# H22R2x_Frontend_1.net
KiCad netlist of a schematic drawn in Altium Designer
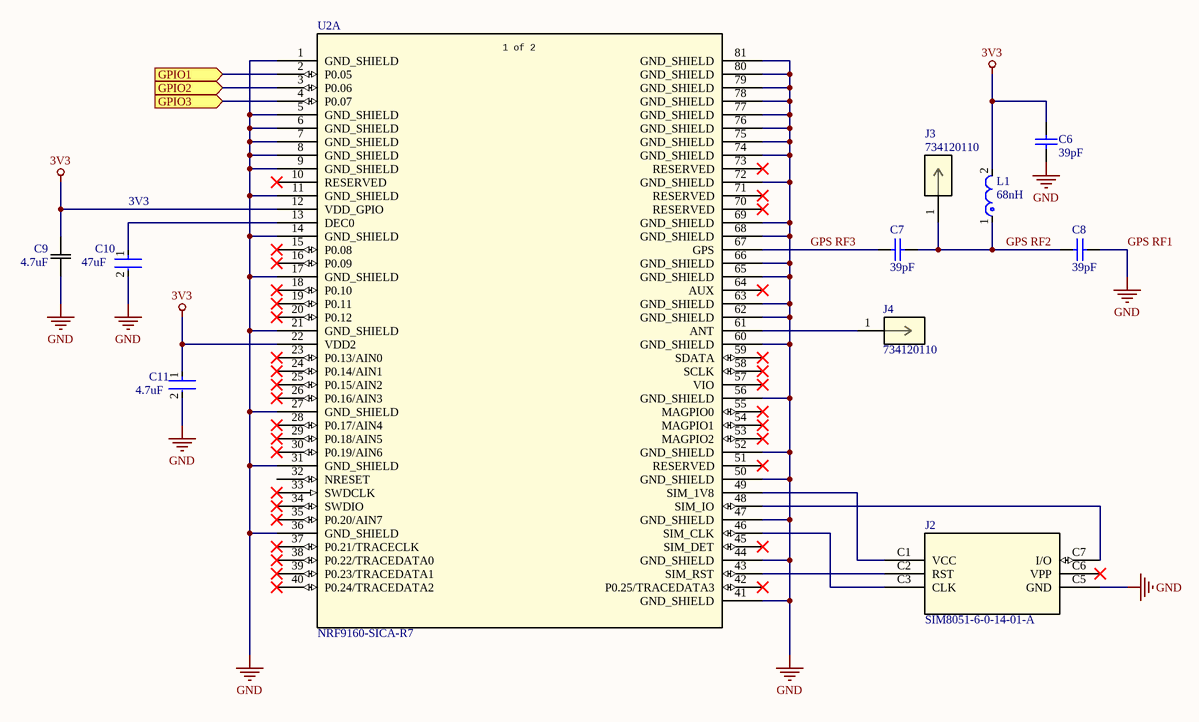
[diagram p0: H22R2x_Frontend 1.SchDoc]

(export (version "E")
  (design (tool "Eeschema 10.0.6"))
  (components
    (comp (ref "C6")
      (value "39pF")
      (footprint "CAPC1005X56X25ML10T15")
      (description "04023A390KAT2A")
      (fields (field (name "MANUFACTURER") "AVX Interconnect / Elco"))
      (libsource (lib "Altium Content Vault") (part "CAP"))
    )
    (comp (ref "C7")
      (value "39pF")
      (footprint "CAPC1005X56X25ML10T15")
      (description "04023A390KAT2A")
      (fields (field (name "MANUFACTURER") "AVX Interconnect / Elco"))
      (libsource (lib "Altium Content Vault") (part "CAP"))
    )
    (comp (ref "C8")
      (value "39pF")
      (footprint "CAPC1005X56X25ML10T15")
      (description "04023A390KAT2A")
      (fields (field (name "MANUFACTURER") "AVX Interconnect / Elco"))
      (libsource (lib "Altium Content Vault") (part "CAP"))
    )
    (comp (ref "C9")
      (value "4.7uF")
      (footprint "CAP_CL10_SAM")
      (description "4.7 µF ±10% 6.3V Ceramic Capacitor X5R 0603 (1608 Metric)")
      (fields
        (field (name "MANUFACTURER_PART_NUMBER") "CL10A475KQ8NNNC")
        (field (name "COPYRIGHT") "Copyright (C) 2025 Ultra Librarian. All rights reserved.")
      )
      (libsource (lib "Tyme Hopkins") (part "CL10A475KQ8NNNC"))
    )
    (comp (ref "C10")
      (value "47uF")
      (footprint "FP-GRM21B-0_2-e0_2_0_7-IPC_B")
      (description "Chip Multilayer Ceramic Capacitors for General Purpose, 0805, 47uF, X5R, 15%, 20%, 6.3V")
      (fields (field (name "TOLERANCE") "20%"))
      (libsource (lib "Altium Content Vault") (part "b4654b650e69147ec39a6b967a45e02"))
    )
    (comp (ref "C11")
      (value "4.7uF")
      (footprint "FP-0603-L_1_6_0_15-W_0_8-MFG")
      (description "Ceramic Capacitor General Use 4.7uF ±10% 10V X6S 0603")
      (fields (field (name "TOLERANCE") "10%"))
      (libsource (lib "Altium Content Vault") (part "11868f565c42a9108669ba33697ecf6"))
    )
    (comp (ref "J2")
      (value "SIM8051-6-0-14-01-A")
      (footprint "SIM8051-6-0-14-01-A_GCT")
      (description "Description")
      (fields (field (name "COPYRIGHT") "Copyright (C) 2025 Ultra Librarian. All rights reserved."))
      (libsource (lib "Tyme Hopkins") (part "SIM8051-6-0-14-01-A"))
    )
    (comp (ref "J3")
      (value "734120110")
      (footprint "CONN_73412-0110_MOL")
      (description "MCRF Jack, Straight, PCB Receptacle, Surface Mount, 1.25mm Mounted Height, 50 Ohms")
      (fields (field (name "COPYRIGHT") "Copyright (C) 2025 Ultra Librarian. All rights reserved."))
      (libsource (lib "Tyme Hopkins") (part "734120110"))
    )
    (comp (ref "J4")
      (value "734120110")
      (footprint "CONN_73412-0110_MOL")
      (description "MCRF Jack, Straight, PCB Receptacle, Surface Mount, 1.25mm Mounted Height, 50 Ohms")
      (fields (field (name "COPYRIGHT") "Copyright (C) 2025 Ultra Librarian. All rights reserved."))
      (libsource (lib "") (part "734120110_1"))
    )
    (comp (ref "L1")
      (value "68nH")
      (footprint "FP-LQG18HH_00-MFG")
      (description "Multilayer type RF Inductor 68nH ±5% 0.8Ω 400mA 0603\r\n\r\nLQG18HN68NJ00D")
      (fields (field (name "TOLERANCE") "5%"))
      (libsource (lib "Altium Content Vault") (part "4cc4b267dca4c8e51f7102f422741d8"))
    )
    (comp (ref "U2")
      (value "NRF9160-SICA-R7")
      (footprint "LGA127_16p00X10p50_nRF9160_NOR")
      (description "Description")
      (fields (field (name "COPYRIGHT") "Copyright (C) 2025 Ultra Librarian. All rights reserved."))
      (libsource (lib "Tyme Hopkins") (part "NRF9160-SICA-R7"))
    )
  )
  (nets
    (net (code "1") (name "/GPIO1") (class "Default")
      (node (ref "U2") (pin "2") (pinfunction "P0.05_2") (pintype "bidirectional"))
    )
    (net (code "2") (name "/GPIO2") (class "Default")
      (node (ref "U2") (pin "3") (pinfunction "P0.06_3") (pintype "bidirectional"))
    )
    (net (code "3") (name "/GPIO3") (class "Default")
      (node (ref "U2") (pin "4") (pinfunction "P0.07_4") (pintype "bidirectional"))
    )
    (net (code "4") (name "/GPS RF2") (class "Default")
      (node (ref "C7") (pin "2") (pinfunction "2_2") (pintype "passive"))
      (node (ref "C8") (pin "1") (pinfunction "1_1") (pintype "passive"))
      (node (ref "J3") (pin "1") (pinfunction "1_1") (pintype "passive"))
      (node (ref "L1") (pin "1") (pinfunction "1_1") (pintype "passive"))
    )
    (net (code "5") (name "/GPS RF3") (class "Default")
      (node (ref "C7") (pin "1") (pinfunction "1_1") (pintype "passive"))
      (node (ref "U2") (pin "67") (pinfunction "GPS_67") (pintype "passive"))
    )
    (net (code "6") (name "3V3") (class "Default")
      (node (ref "C11") (pin "1") (pinfunction "1_1") (pintype "passive"))
      (node (ref "C6") (pin "2") (pinfunction "2_2") (pintype "passive"))
      (node (ref "C9") (pin "2") (pinfunction "2_2") (pintype "passive"))
      (node (ref "L1") (pin "2") (pinfunction "2_2") (pintype "passive"))
      (node (ref "U2") (pin "12") (pinfunction "VDD_GPIO_12") (pintype "power_in"))
      (node (ref "U2") (pin "22") (pinfunction "VDD2_22") (pintype "power_in"))
    )
    (net (code "7") (name "GND") (class "Default")
      (node (ref "C10") (pin "2") (pinfunction "2_2") (pintype "passive"))
      (node (ref "C11") (pin "2") (pinfunction "2_2") (pintype "passive"))
      (node (ref "C6") (pin "1") (pinfunction "1_1") (pintype "passive"))
      (node (ref "C8") (pin "2") (pinfunction "2_2") (pintype "passive"))
      (node (ref "C9") (pin "1") (pinfunction "1_1") (pintype "passive"))
      (node (ref "J2") (pin "C5") (pinfunction "GND_C5") (pintype "power_in"))
      (node (ref "U2") (pin "1") (pinfunction "GND_SHIELD_1") (pintype "power_in"))
      (node (ref "U2") (pin "11") (pinfunction "GND_SHIELD_11") (pintype "power_in"))
      (node (ref "U2") (pin "14") (pinfunction "GND_SHIELD_14") (pintype "power_in"))
      (node (ref "U2") (pin "17") (pinfunction "GND_SHIELD_17") (pintype "power_in"))
      (node (ref "U2") (pin "21") (pinfunction "GND_SHIELD_21") (pintype "power_in"))
      (node (ref "U2") (pin "27") (pinfunction "GND_SHIELD_27") (pintype "power_in"))
      (node (ref "U2") (pin "31") (pinfunction "GND_SHIELD_31") (pintype "power_in"))
      (node (ref "U2") (pin "36") (pinfunction "GND_SHIELD_36") (pintype "power_in"))
      (node (ref "U2") (pin "41") (pinfunction "GND_SHIELD_41") (pintype "power_in"))
      (node (ref "U2") (pin "44") (pinfunction "GND_SHIELD_44") (pintype "power_in"))
      (node (ref "U2") (pin "47") (pinfunction "GND_SHIELD_47") (pintype "power_in"))
      (node (ref "U2") (pin "5") (pinfunction "GND_SHIELD_5") (pintype "power_in"))
      (node (ref "U2") (pin "50") (pinfunction "GND_SHIELD_50") (pintype "power_in"))
      (node (ref "U2") (pin "52") (pinfunction "GND_SHIELD_52") (pintype "power_in"))
      (node (ref "U2") (pin "56") (pinfunction "GND_SHIELD_56") (pintype "power_in"))
      (node (ref "U2") (pin "6") (pinfunction "GND_SHIELD_6") (pintype "power_in"))
      (node (ref "U2") (pin "60") (pinfunction "GND_SHIELD_60") (pintype "power_in"))
      (node (ref "U2") (pin "62") (pinfunction "GND_SHIELD_62") (pintype "power_in"))
      (node (ref "U2") (pin "63") (pinfunction "GND_SHIELD_63") (pintype "power_in"))
      (node (ref "U2") (pin "65") (pinfunction "GND_SHIELD_65") (pintype "power_in"))
      (node (ref "U2") (pin "66") (pinfunction "GND_SHIELD_66") (pintype "power_in"))
      (node (ref "U2") (pin "68") (pinfunction "GND_SHIELD_68") (pintype "power_in"))
      (node (ref "U2") (pin "69") (pinfunction "GND_SHIELD_69") (pintype "power_in"))
      (node (ref "U2") (pin "7") (pinfunction "GND_SHIELD_7") (pintype "power_in"))
      (node (ref "U2") (pin "72") (pinfunction "GND_SHIELD_72") (pintype "power_in"))
      (node (ref "U2") (pin "74") (pinfunction "GND_SHIELD_74") (pintype "power_in"))
      (node (ref "U2") (pin "75") (pinfunction "GND_SHIELD_75") (pintype "power_in"))
      (node (ref "U2") (pin "76") (pinfunction "GND_SHIELD_76") (pintype "power_in"))
      (node (ref "U2") (pin "77") (pinfunction "GND_SHIELD_77") (pintype "power_in"))
      (node (ref "U2") (pin "78") (pinfunction "GND_SHIELD_78") (pintype "power_in"))
      (node (ref "U2") (pin "79") (pinfunction "GND_SHIELD_79") (pintype "power_in"))
      (node (ref "U2") (pin "8") (pinfunction "GND_SHIELD_8") (pintype "power_in"))
      (node (ref "U2") (pin "80") (pinfunction "GND_SHIELD_80") (pintype "power_in"))
      (node (ref "U2") (pin "81") (pinfunction "GND_SHIELD_81") (pintype "power_in"))
      (node (ref "U2") (pin "9") (pinfunction "GND_SHIELD_9") (pintype "power_in"))
    )
    (net (code "8") (name "Net-(J2-CLK)") (class "Default")
      (node (ref "J2") (pin "C3") (pinfunction "CLK_C3") (pintype "passive"))
      (node (ref "U2") (pin "46") (pinfunction "SIM_CLK_46") (pintype "bidirectional"))
    )
    (net (code "9") (name "Net-(J2-I{slash}O)") (class "Default")
      (node (ref "J2") (pin "C7") (pinfunction "I/O_C7") (pintype "bidirectional"))
      (node (ref "U2") (pin "48") (pinfunction "SIM_IO_48") (pintype "bidirectional"))
    )
    (net (code "10") (name "Net-(J2-RST)") (class "Default")
      (node (ref "J2") (pin "C2") (pinfunction "RST_C2") (pintype "passive"))
      (node (ref "U2") (pin "43") (pinfunction "SIM_RST_43") (pintype "bidirectional"))
    )
    (net (code "11") (name "Net-(J2-VCC)") (class "Default")
      (node (ref "J2") (pin "C1") (pinfunction "VCC_C1") (pintype "power_in"))
      (node (ref "U2") (pin "49") (pinfunction "SIM_1V8_49") (pintype "power_in"))
    )
    (net (code "12") (name "Net-(U2A-ANT)") (class "Default")
      (node (ref "J4") (pin "1") (pinfunction "1_1") (pintype "passive"))
      (node (ref "U2") (pin "61") (pinfunction "ANT_61") (pintype "passive"))
    )
    (net (code "13") (name "Net-(U2A-DEC0)") (class "Default")
      (node (ref "C10") (pin "1") (pinfunction "1_1") (pintype "passive"))
      (node (ref "U2") (pin "13") (pinfunction "DEC0_13") (pintype "power_in"))
    )
    (net (code "14") (name "unconnected-(J2-VPP-PadC6)") (class "Default")
      (node (ref "J2") (pin "C6") (pinfunction "VPP_C6") (pintype "power_in+no_connect"))
    )
    (net (code "15") (name "unconnected-(U2A-AUX-Pad64)") (class "Default")
      (node (ref "U2") (pin "64") (pinfunction "AUX_64") (pintype "passive+no_connect"))
    )
    (net (code "16") (name "unconnected-(U2A-MAGPIO0-Pad55)") (class "Default")
      (node (ref "U2") (pin "55") (pinfunction "MAGPIO0_55") (pintype "bidirectional+no_connect"))
    )
    (net (code "17") (name "unconnected-(U2A-MAGPIO1-Pad54)") (class "Default")
      (node (ref "U2") (pin "54") (pinfunction "MAGPIO1_54") (pintype "bidirectional+no_connect"))
    )
    (net (code "18") (name "unconnected-(U2A-MAGPIO2-Pad53)") (class "Default")
      (node (ref "U2") (pin "53") (pinfunction "MAGPIO2_53") (pintype "bidirectional+no_connect"))
    )
    (net (code "19") (name "unconnected-(U2A-NRESET-Pad32)") (class "Default")
      (node (ref "U2") (pin "32") (pinfunction "NRESET_32") (pintype "bidirectional"))
    )
    (net (code "20") (name "unconnected-(U2A-P0.08-Pad15)") (class "Default")
      (node (ref "U2") (pin "15") (pinfunction "P0.08_15") (pintype "bidirectional+no_connect"))
    )
    (net (code "21") (name "unconnected-(U2A-P0.09-Pad16)") (class "Default")
      (node (ref "U2") (pin "16") (pinfunction "P0.09_16") (pintype "bidirectional+no_connect"))
    )
    (net (code "22") (name "unconnected-(U2A-P0.10-Pad18)") (class "Default")
      (node (ref "U2") (pin "18") (pinfunction "P0.10_18") (pintype "bidirectional+no_connect"))
    )
    (net (code "23") (name "unconnected-(U2A-P0.11-Pad19)") (class "Default")
      (node (ref "U2") (pin "19") (pinfunction "P0.11_19") (pintype "bidirectional+no_connect"))
    )
    (net (code "24") (name "unconnected-(U2A-P0.12-Pad20)") (class "Default")
      (node (ref "U2") (pin "20") (pinfunction "P0.12_20") (pintype "bidirectional+no_connect"))
    )
    (net (code "25") (name "unconnected-(U2A-P0.13{slash}AIN0-Pad23)") (class "Default")
      (node (ref "U2") (pin "23") (pinfunction "P0.13/AIN0_23") (pintype "bidirectional+no_connect"))
    )
    (net (code "26") (name "unconnected-(U2A-P0.14{slash}AIN1-Pad24)") (class "Default")
      (node (ref "U2") (pin "24") (pinfunction "P0.14/AIN1_24") (pintype "bidirectional+no_connect"))
    )
    (net (code "27") (name "unconnected-(U2A-P0.15{slash}AIN2-Pad25)") (class "Default")
      (node (ref "U2") (pin "25") (pinfunction "P0.15/AIN2_25") (pintype "bidirectional+no_connect"))
    )
    (net (code "28") (name "unconnected-(U2A-P0.16{slash}AIN3-Pad26)") (class "Default")
      (node (ref "U2") (pin "26") (pinfunction "P0.16/AIN3_26") (pintype "bidirectional+no_connect"))
    )
    (net (code "29") (name "unconnected-(U2A-P0.17{slash}AIN4-Pad28)") (class "Default")
      (node (ref "U2") (pin "28") (pinfunction "P0.17/AIN4_28") (pintype "bidirectional+no_connect"))
    )
    (net (code "30") (name "unconnected-(U2A-P0.18{slash}AIN5-Pad29)") (class "Default")
      (node (ref "U2") (pin "29") (pinfunction "P0.18/AIN5_29") (pintype "bidirectional+no_connect"))
    )
    (net (code "31") (name "unconnected-(U2A-P0.19{slash}AIN6-Pad30)") (class "Default")
      (node (ref "U2") (pin "30") (pinfunction "P0.19/AIN6_30") (pintype "bidirectional+no_connect"))
    )
    (net (code "32") (name "unconnected-(U2A-P0.20{slash}AIN7-Pad35)") (class "Default")
      (node (ref "U2") (pin "35") (pinfunction "P0.20/AIN7_35") (pintype "bidirectional+no_connect"))
    )
    (net (code "33") (name "unconnected-(U2A-P0.21{slash}TRACECLK-Pad37)") (class "Default")
      (node (ref "U2") (pin "37") (pinfunction "P0.21/TRACECLK_37") (pintype "bidirectional+no_connect"))
    )
    (net (code "34") (name "unconnected-(U2A-P0.22{slash}TRACEDATA0-Pad38)") (class "Default")
      (node (ref "U2") (pin "38") (pinfunction "P0.22/TRACEDATA0_38") (pintype "bidirectional+no_connect"))
    )
    (net (code "35") (name "unconnected-(U2A-P0.23{slash}TRACEDATA1-Pad39)") (class "Default")
      (node (ref "U2") (pin "39") (pinfunction "P0.23/TRACEDATA1_39") (pintype "bidirectional+no_connect"))
    )
    (net (code "36") (name "unconnected-(U2A-P0.24{slash}TRACEDATA2-Pad40)") (class "Default")
      (node (ref "U2") (pin "40") (pinfunction "P0.24/TRACEDATA2_40") (pintype "bidirectional+no_connect"))
    )
    (net (code "37") (name "unconnected-(U2A-P0.25{slash}TRACEDATA3-Pad42)") (class "Default")
      (node (ref "U2") (pin "42") (pinfunction "P0.25/TRACEDATA3_42") (pintype "bidirectional+no_connect"))
    )
    (net (code "38") (name "unconnected-(U2A-RESERVED-Pad10)") (class "Default")
      (node (ref "U2") (pin "10") (pinfunction "RESERVED_10") (pintype "passive+no_connect"))
    )
    (net (code "39") (name "unconnected-(U2A-RESERVED-Pad51)") (class "Default")
      (node (ref "U2") (pin "51") (pinfunction "RESERVED_51") (pintype "passive+no_connect"))
    )
    (net (code "40") (name "unconnected-(U2A-RESERVED-Pad70)") (class "Default")
      (node (ref "U2") (pin "70") (pinfunction "RESERVED_70") (pintype "passive+no_connect"))
    )
    (net (code "41") (name "unconnected-(U2A-RESERVED-Pad71)") (class "Default")
      (node (ref "U2") (pin "71") (pinfunction "RESERVED_71") (pintype "passive+no_connect"))
    )
    (net (code "42") (name "unconnected-(U2A-RESERVED-Pad73)") (class "Default")
      (node (ref "U2") (pin "73") (pinfunction "RESERVED_73") (pintype "passive+no_connect"))
    )
    (net (code "43") (name "unconnected-(U2A-SCLK-Pad58)") (class "Default")
      (node (ref "U2") (pin "58") (pinfunction "SCLK_58") (pintype "bidirectional+no_connect"))
    )
    (net (code "44") (name "unconnected-(U2A-SDATA-Pad59)") (class "Default")
      (node (ref "U2") (pin "59") (pinfunction "SDATA_59") (pintype "bidirectional+no_connect"))
    )
    (net (code "45") (name "unconnected-(U2A-SIM_DET-Pad45)") (class "Default")
      (node (ref "U2") (pin "45") (pinfunction "SIM_DET_45") (pintype "bidirectional+no_connect"))
    )
    (net (code "46") (name "unconnected-(U2A-SWDCLK-Pad33)") (class "Default")
      (node (ref "U2") (pin "33") (pinfunction "SWDCLK_33") (pintype "input+no_connect"))
    )
    (net (code "47") (name "unconnected-(U2A-SWDIO-Pad34)") (class "Default")
      (node (ref "U2") (pin "34") (pinfunction "SWDIO_34") (pintype "bidirectional+no_connect"))
    )
    (net (code "48") (name "unconnected-(U2A-VIO-Pad57)") (class "Default")
      (node (ref "U2") (pin "57") (pinfunction "VIO_57") (pintype "power_in+no_connect"))
    )
  )
)
